# Sensors.net
KiCad netlist of a schematic drawn in Altium Designer
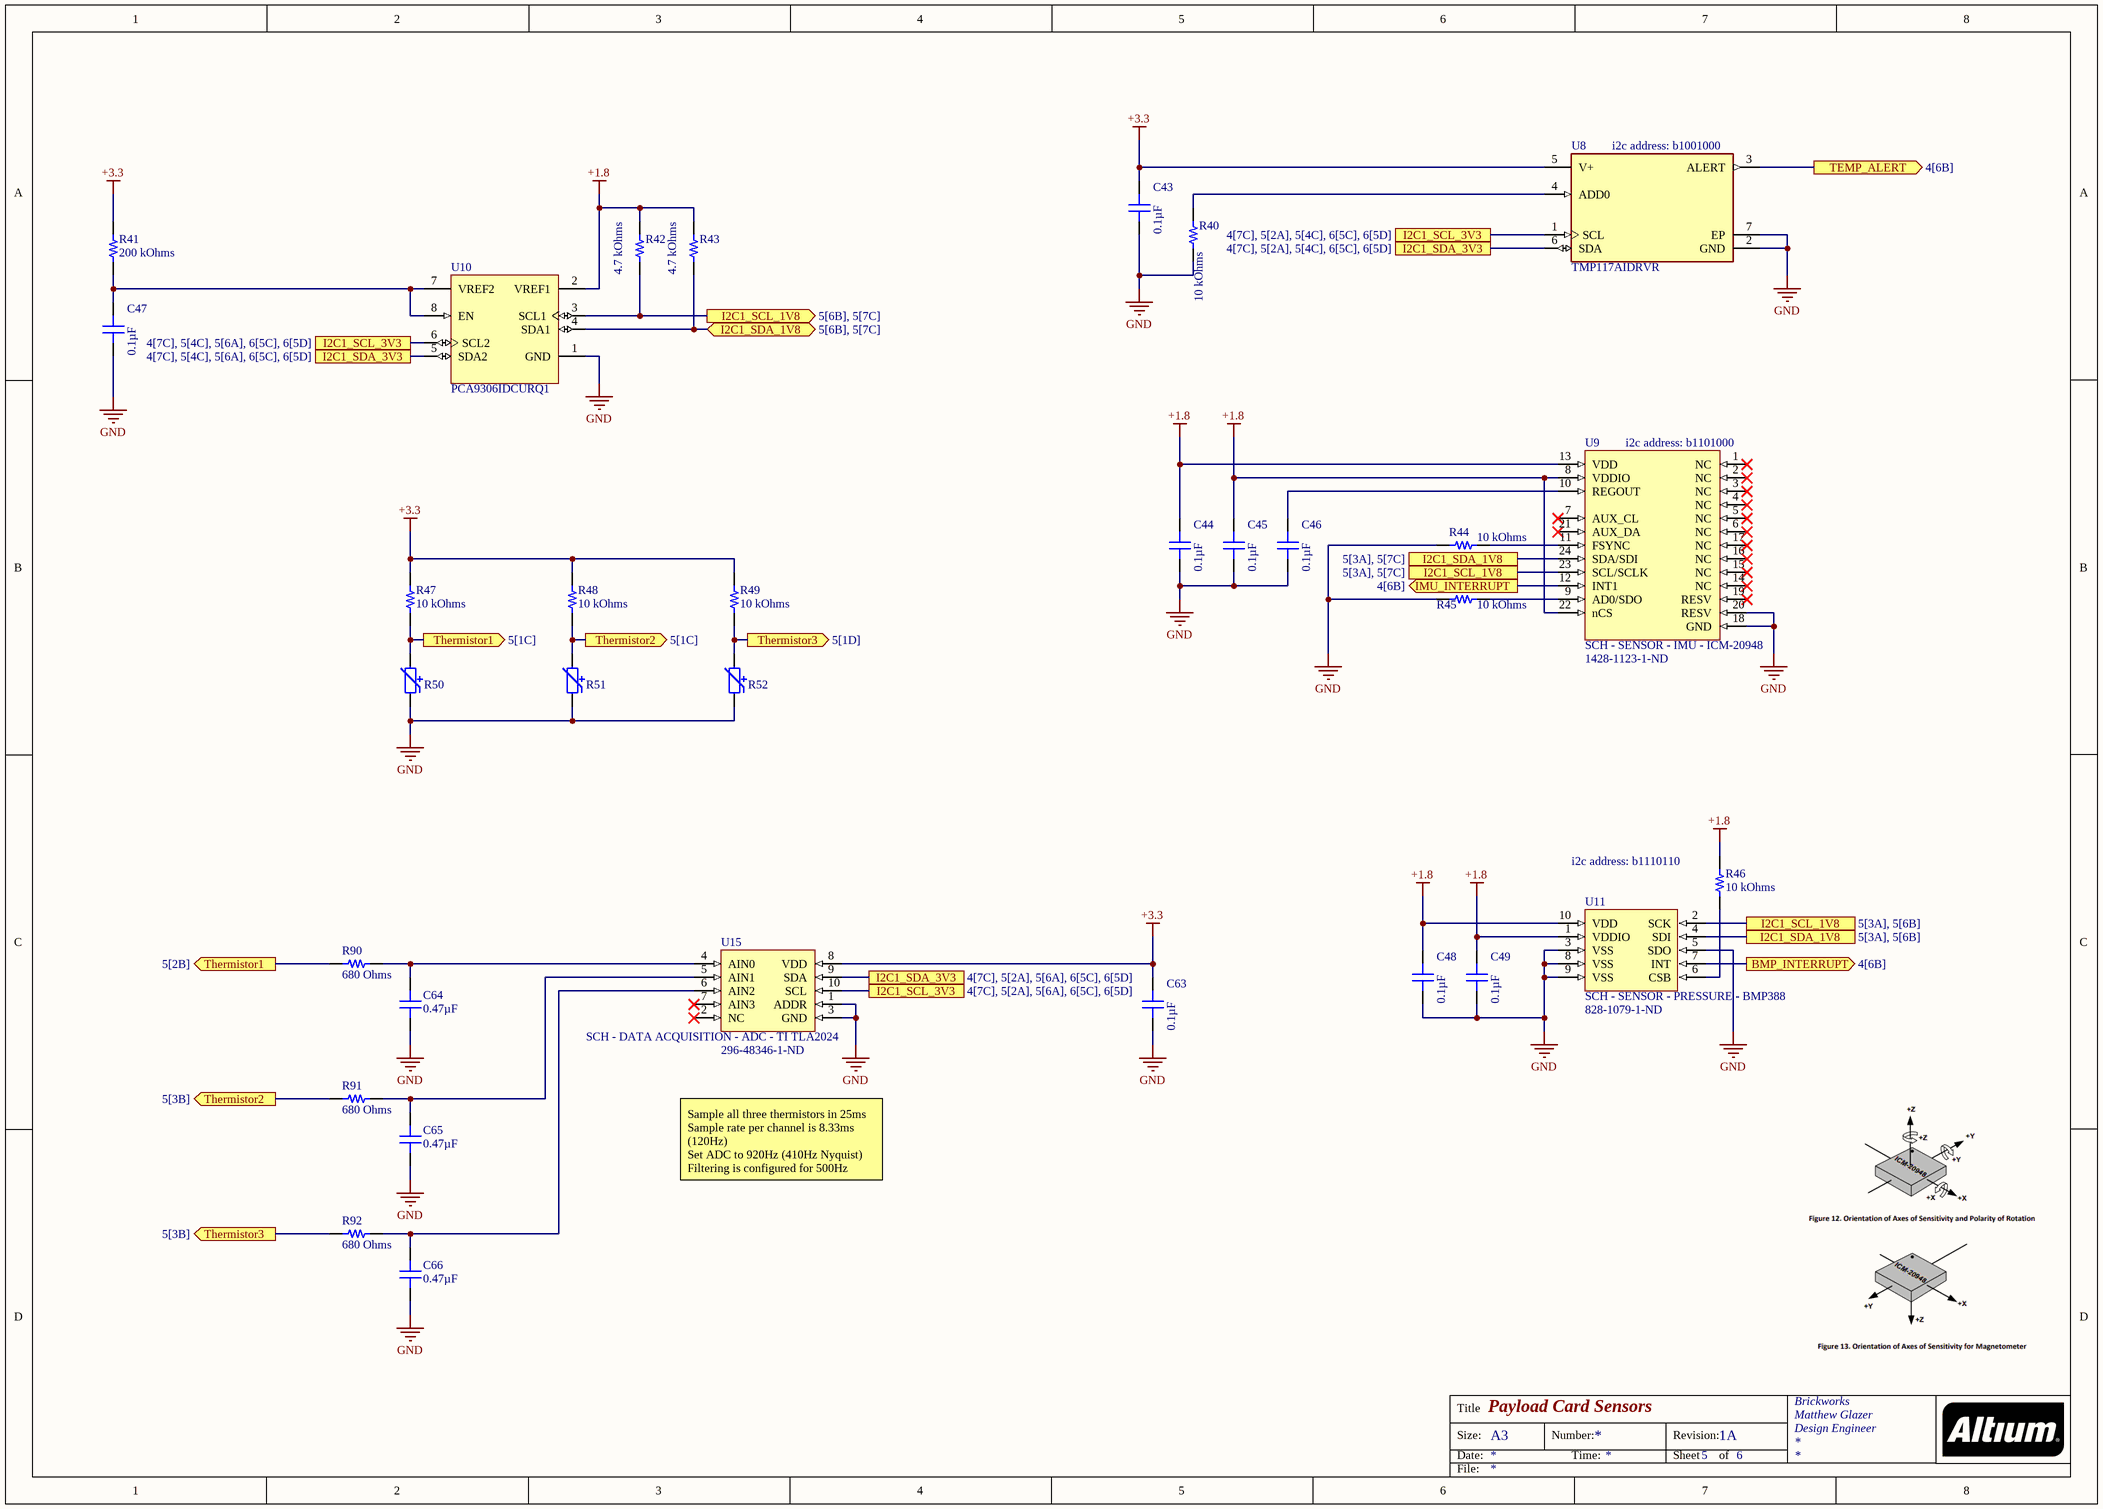
[diagram p0: Sensors.SchDoc]

(export (version "E")
  (design (tool "Eeschema 10.0.6"))
  (components
    (comp (ref "C43")
      (value "0.1µF")
      (footprint "CAP 0603_1608")
      (description "CAP CER 0.1UF 25V X7R 0603")
      (fields
        (field (name "PART NUMBER") "CL10B104KA8WPNC")
        (field (name "MANUFACTURER") "Samsung Electro-Mechanics")
      )
      (libsource (lib "Celestial Altium Library - altium_library") (part "Capacitor"))
    )
    (comp (ref "C44")
      (value "0.1µF")
      (footprint "CAP 0603_1608")
      (description "CAP CER 0.1UF 25V X7R 0603")
      (fields
        (field (name "PART NUMBER") "CL10B104KA8WPNC")
        (field (name "MANUFACTURER") "Samsung Electro-Mechanics")
      )
      (libsource (lib "Celestial Altium Library - altium_library") (part "Capacitor"))
    )
    (comp (ref "C45")
      (value "0.1µF")
      (footprint "CAP 0603_1608")
      (description "CAP CER 0.1UF 25V X7R 0603")
      (fields
        (field (name "PART NUMBER") "CL10B104KA8WPNC")
        (field (name "MANUFACTURER") "Samsung Electro-Mechanics")
      )
      (libsource (lib "Celestial Altium Library - altium_library") (part "Capacitor"))
    )
    (comp (ref "C46")
      (value "0.1µF")
      (footprint "CAP 0603_1608")
      (description "CAP CER 0.1UF 25V X7R 0603")
      (fields
        (field (name "PART NUMBER") "CL10B104KA8WPNC")
        (field (name "MANUFACTURER") "Samsung Electro-Mechanics")
      )
      (libsource (lib "Celestial Altium Library - altium_library") (part "Capacitor"))
    )
    (comp (ref "C47")
      (value "0.1µF")
      (footprint "CAP 0603_1608")
      (description "CAP CER 0.1UF 25V X7R 0603")
      (fields
        (field (name "PART NUMBER") "CL10B104KA8WPNC")
        (field (name "MANUFACTURER") "Samsung Electro-Mechanics")
      )
      (libsource (lib "Celestial Altium Library - altium_library") (part "Capacitor"))
    )
    (comp (ref "C48")
      (value "0.1µF")
      (footprint "CAP 0603_1608")
      (description "CAP CER 0.1UF 25V X7R 0603")
      (fields
        (field (name "PART NUMBER") "CL10B104KA8WPNC")
        (field (name "MANUFACTURER") "Samsung Electro-Mechanics")
      )
      (libsource (lib "Celestial Altium Library - altium_library") (part "Capacitor"))
    )
    (comp (ref "C49")
      (value "0.1µF")
      (footprint "CAP 0603_1608")
      (description "CAP CER 0.1UF 25V X7R 0603")
      (fields
        (field (name "PART NUMBER") "CL10B104KA8WPNC")
        (field (name "MANUFACTURER") "Samsung Electro-Mechanics")
      )
      (libsource (lib "Celestial Altium Library - altium_library") (part "Capacitor"))
    )
    (comp (ref "C63")
      (value "0.1µF")
      (footprint "CAP 0603_1608")
      (description "CAP CER 0.1UF 25V X7R 0603")
      (fields
        (field (name "PART NUMBER") "CL10B104KA8WPNC")
        (field (name "MANUFACTURER") "Samsung Electro-Mechanics")
      )
      (libsource (lib "Celestial Altium Library - altium_library") (part "Capacitor"))
    )
    (comp (ref "C64")
      (value "0.47µF")
      (footprint "CAP 0603_1608")
      (description "CAP CER 0.47UF 16V X5R 0603")
      (fields (field (name "PART NUMBER") "C0603C474K4PACTU") (field (name "MANUFACTURER") "KEMET"))
      (libsource (lib "Celestial Altium Library - altium_library") (part "Capacitor"))
    )
    (comp (ref "C65")
      (value "0.47µF")
      (footprint "CAP 0603_1608")
      (description "CAP CER 0.47UF 16V X5R 0603")
      (fields (field (name "PART NUMBER") "C0603C474K4PACTU") (field (name "MANUFACTURER") "KEMET"))
      (libsource (lib "Celestial Altium Library - altium_library") (part "Capacitor"))
    )
    (comp (ref "C66")
      (value "0.47µF")
      (footprint "CAP 0603_1608")
      (description "CAP CER 0.47UF 16V X5R 0603")
      (fields (field (name "PART NUMBER") "C0603C474K4PACTU") (field (name "MANUFACTURER") "KEMET"))
      (libsource (lib "Celestial Altium Library - altium_library") (part "Capacitor"))
    )
    (comp (ref "R40")
      (value "10 kOhms")
      (footprint "RES 0603_1608")
      (description "RES 10K OHM 5% 1/10W 0603")
      (fields
        (field (name "PART NUMBER") "RMCF0603JT10K0")
        (field (name "MANUFACTURER") "Stackpole Electronics Inc")
      )
      (libsource (lib "Celestial Altium Library - altium_library") (part "Resistor"))
    )
    (comp (ref "R41")
      (value "200 kOhms")
      (footprint "RES 0603_1608")
      (description "RES 200K OHM 1% 1/10W 0603")
      (fields
        (field (name "PART NUMBER") "RMCF0603FT200K")
        (field (name "MANUFACTURER") "Stackpole Electronics Inc")
      )
      (libsource (lib "Celestial Altium Library - altium_library") (part "Resistor"))
    )
    (comp (ref "R42")
      (value "4.7 kOhms")
      (footprint "RES 0603_1608")
      (description "RES 4.7K OHM 1% 1/10W 0603")
      (fields
        (field (name "PART NUMBER") "RMCF0603FT4K70")
        (field (name "MANUFACTURER") "Stackpole Electronics Inc")
      )
      (libsource (lib "Celestial Altium Library - altium_library") (part "Resistor"))
    )
    (comp (ref "R43")
      (value "4.7 kOhms")
      (footprint "RES 0603_1608")
      (description "RES 4.7K OHM 1% 1/10W 0603")
      (fields
        (field (name "PART NUMBER") "RMCF0603FT4K70")
        (field (name "MANUFACTURER") "Stackpole Electronics Inc")
      )
      (libsource (lib "Celestial Altium Library - altium_library") (part "Resistor"))
    )
    (comp (ref "R44")
      (value "10 kOhms")
      (footprint "RES 0603_1608")
      (description "RES 10K OHM 5% 1/10W 0603")
      (fields
        (field (name "PART NUMBER") "RMCF0603JT10K0")
        (field (name "MANUFACTURER") "Stackpole Electronics Inc")
      )
      (libsource (lib "Celestial Altium Library - altium_library") (part "Resistor"))
    )
    (comp (ref "R45")
      (value "10 kOhms")
      (footprint "RES 0603_1608")
      (description "RES 10K OHM 5% 1/10W 0603")
      (fields
        (field (name "PART NUMBER") "RMCF0603JT10K0")
        (field (name "MANUFACTURER") "Stackpole Electronics Inc")
      )
      (libsource (lib "Celestial Altium Library - altium_library") (part "Resistor"))
    )
    (comp (ref "R46")
      (value "10 kOhms")
      (footprint "RES 0603_1608")
      (description "RES 10K OHM 5% 1/10W 0603")
      (fields
        (field (name "PART NUMBER") "RMCF0603JT10K0")
        (field (name "MANUFACTURER") "Stackpole Electronics Inc")
      )
      (libsource (lib "Celestial Altium Library - altium_library") (part "Resistor"))
    )
    (comp (ref "R47")
      (value "10 kOhms")
      (footprint "RES 0603_1608")
      (description "RES 10K OHM 1% 1/10W 0603")
      (fields
        (field (name "PART NUMBER") "RMCF0603FT10K0")
        (field (name "MANUFACTURER") "Stackpole Electronics Inc")
      )
      (libsource (lib "Celestial Altium Library - altium_library") (part "Resistor"))
    )
    (comp (ref "R48")
      (value "10 kOhms")
      (footprint "RES 0603_1608")
      (description "RES 10K OHM 1% 1/10W 0603")
      (fields
        (field (name "PART NUMBER") "RMCF0603FT10K0")
        (field (name "MANUFACTURER") "Stackpole Electronics Inc")
      )
      (libsource (lib "Celestial Altium Library - altium_library") (part "Resistor"))
    )
    (comp (ref "R49")
      (value "10 kOhms")
      (footprint "RES 0603_1608")
      (description "RES 10K OHM 1% 1/10W 0603")
      (fields
        (field (name "PART NUMBER") "RMCF0603FT10K0")
        (field (name "MANUFACTURER") "Stackpole Electronics Inc")
      )
      (libsource (lib "Celestial Altium Library - altium_library") (part "Resistor"))
    )
    (comp (ref "R50")
      (value "10 kOhms")
      (footprint "PTC 0402_1005")
      (description "SENSOR PTC 10KOHM 1% X1SON")
      (fields (field (name "MANUFACTURER") "Texas Instruments") (field (name "PART NUMBER") "TMP6131DECR"))
      (libsource (lib "Celestial Altium Library - altium_library") (part "Thermistor PTC"))
    )
    (comp (ref "R51")
      (value "10 kOhms")
      (footprint "PTC 0402_1005")
      (description "SENSOR PTC 10KOHM 1% X1SON")
      (fields (field (name "MANUFACTURER") "Texas Instruments") (field (name "PART NUMBER") "TMP6131DECR"))
      (libsource (lib "Celestial Altium Library - altium_library") (part "Thermistor PTC"))
    )
    (comp (ref "R52")
      (value "10 kOhms")
      (footprint "PTC 0402_1005")
      (description "SENSOR PTC 10KOHM 1% X1SON")
      (fields (field (name "MANUFACTURER") "Texas Instruments") (field (name "PART NUMBER") "TMP6131DECR"))
      (libsource (lib "Celestial Altium Library - altium_library") (part "Thermistor PTC"))
    )
    (comp (ref "R90")
      (value "680 Ohms")
      (footprint "RES 0603_1608")
      (description "RES 680 OHM 1% 1/10W 0603")
      (fields
        (field (name "PART NUMBER") "RMCF0603FT680R")
        (field (name "MANUFACTURER") "Stackpole Electronics Inc")
      )
      (libsource (lib "Celestial Altium Library - altium_library") (part "Resistor"))
    )
    (comp (ref "R91")
      (value "680 Ohms")
      (footprint "RES 0603_1608")
      (description "RES 680 OHM 1% 1/10W 0603")
      (fields
        (field (name "PART NUMBER") "RMCF0603FT680R")
        (field (name "MANUFACTURER") "Stackpole Electronics Inc")
      )
      (libsource (lib "Celestial Altium Library - altium_library") (part "Resistor"))
    )
    (comp (ref "R92")
      (value "680 Ohms")
      (footprint "RES 0603_1608")
      (description "RES 680 OHM 1% 1/10W 0603")
      (fields
        (field (name "PART NUMBER") "RMCF0603FT680R")
        (field (name "MANUFACTURER") "Stackpole Electronics Inc")
      )
      (libsource (lib "Celestial Altium Library - altium_library") (part "Resistor"))
    )
    (comp (ref "U8")
      (value "TMP117AIDRVR")
      (footprint "FP-DRV0006A-MFG")
      (description "TEMPERATURE SENSOR")
      (fields
        (field (name "OCTOPART") "https://octopart.com/tmp117aidrvr-texas+instruments-95511044")
        (field (name "MANUFACTURER") "Texas Instruments")
      )
      (libsource (lib "Altium Content Vault") (part "bceab6869a9cb85cf5675529ee35ce4"))
    )
    (comp (ref "U9")
      (value "SCH - SENSOR - IMU - ICM-20948")
      (footprint "PCB - LEADLESS - QFN - TDK 24-TFQFN")
      (fields (field (name "SUPPLIER PART NUMBER 1") "1428-1123-1-ND"))
      (libsource (lib "HAB_ICs") (part "SCH - SENSOR - IMU - ICM-20948"))
    )
    (comp (ref "U10")
      (value "PCA9306IDCURQ1")
      (footprint "DCU0008A_M")
      (fields (field (name "MANUFACTURER") "Texas Instruments"))
      (libsource (lib "Altium Content Vault") (part "TI-PCA9306-Q1-US8_DCU-8"))
    )
    (comp (ref "U11")
      (value "SCH - SENSOR - PRESSURE - BMP388")
      (footprint "PCB - LEADLESS - BOSCH LGA10")
      (fields (field (name "SUPPLIER PART NUMBER 1") "828-1079-1-ND"))
      (libsource (lib "HAB_ICs") (part "SCH - SENSOR - PRESSURE - BMP388"))
    )
    (comp (ref "U15")
      (value "SCH - DATA ACQUISITION - ADC - TI TLA2024")
      (footprint "PCB - LEADLESS - QFN - TI X2QFN-10")
      (fields (field (name "SUPPLIER PART NUMBER 1") "296-48346-1-ND"))
      (libsource (lib "HAB_ICs") (part "SCH - DATA ACQUISITION - ADC - TI TLA2024"))
    )
  )
  (nets
    (net (code "1") (name "+1.8") (class "Default")
      (node (ref "C44") (pin "2") (pinfunction "2_2") (pintype "passive"))
      (node (ref "C45") (pin "2") (pinfunction "2_2") (pintype "passive"))
      (node (ref "C48") (pin "2") (pinfunction "2_2") (pintype "passive"))
      (node (ref "C49") (pin "2") (pinfunction "2_2") (pintype "passive"))
      (node (ref "R42") (pin "2") (pinfunction "2_2") (pintype "passive"))
      (node (ref "R43") (pin "2") (pinfunction "2_2") (pintype "passive"))
      (node (ref "R46") (pin "1") (pinfunction "1_1") (pintype "passive"))
      (node (ref "U10") (pin "2") (pinfunction "VREF1_2") (pintype "power_in"))
      (node (ref "U11") (pin "1") (pinfunction "VDDIO_1") (pintype "input"))
      (node (ref "U11") (pin "10") (pinfunction "VDD_10") (pintype "input"))
      (node (ref "U9") (pin "13") (pinfunction "VDD_13") (pintype "input"))
      (node (ref "U9") (pin "22") (pinfunction "nCS_22") (pintype "input"))
      (node (ref "U9") (pin "8") (pinfunction "VDDIO_8") (pintype "input"))
    )
    (net (code "2") (name "+3.3") (class "Default")
      (node (ref "C43") (pin "2") (pinfunction "2_2") (pintype "passive"))
      (node (ref "C63") (pin "2") (pinfunction "2_2") (pintype "passive"))
      (node (ref "R41") (pin "2") (pinfunction "2_2") (pintype "passive"))
      (node (ref "R47") (pin "2") (pinfunction "2_2") (pintype "passive"))
      (node (ref "R48") (pin "2") (pinfunction "2_2") (pintype "passive"))
      (node (ref "R49") (pin "2") (pinfunction "2_2") (pintype "passive"))
      (node (ref "U15") (pin "8") (pinfunction "VDD_8") (pintype "input"))
      (node (ref "U8") (pin "5") (pinfunction "V+_5") (pintype "power_in"))
    )
    (net (code "3") (name "/BMP_INTERRUPT") (class "Default")
      (node (ref "U11") (pin "7") (pinfunction "INT_7") (pintype "input"))
    )
    (net (code "4") (name "/I2C1_SCL_1V8") (class "Default")
      (node (ref "R42") (pin "1") (pinfunction "1_1") (pintype "passive"))
      (node (ref "U10") (pin "3") (pinfunction "SCL1_3") (pintype "bidirectional"))
      (node (ref "U11") (pin "2") (pinfunction "SCK_2") (pintype "input"))
      (node (ref "U9") (pin "23") (pinfunction "SCL/SCLK_23") (pintype "input"))
    )
    (net (code "5") (name "/I2C1_SCL_3V3") (class "Default")
      (node (ref "U10") (pin "6") (pinfunction "SCL2_6") (pintype "bidirectional"))
      (node (ref "U15") (pin "10") (pinfunction "SCL_10") (pintype "input"))
      (node (ref "U8") (pin "1") (pinfunction "SCL_1") (pintype "input"))
    )
    (net (code "6") (name "/I2C1_SDA_1V8") (class "Default")
      (node (ref "R43") (pin "1") (pinfunction "1_1") (pintype "passive"))
      (node (ref "U10") (pin "4") (pinfunction "SDA1_4") (pintype "bidirectional"))
      (node (ref "U11") (pin "4") (pinfunction "SDI_4") (pintype "input"))
      (node (ref "U9") (pin "24") (pinfunction "SDA/SDI_24") (pintype "input"))
    )
    (net (code "7") (name "/I2C1_SDA_3V3") (class "Default")
      (node (ref "U10") (pin "5") (pinfunction "SDA2_5") (pintype "bidirectional"))
      (node (ref "U15") (pin "9") (pinfunction "SDA_9") (pintype "input"))
      (node (ref "U8") (pin "6") (pinfunction "SDA_6") (pintype "bidirectional"))
    )
    (net (code "8") (name "/IMU_INTERRUPT") (class "Default")
      (node (ref "U9") (pin "12") (pinfunction "INT1_12") (pintype "input"))
    )
    (net (code "9") (name "/TEMP_ALERT") (class "Default")
      (node (ref "U8") (pin "3") (pinfunction "ALERT_3") (pintype "output"))
    )
    (net (code "10") (name "/Thermistor1") (class "Default")
      (node (ref "R47") (pin "1") (pinfunction "1_1") (pintype "passive"))
      (node (ref "R50") (pin "2") (pinfunction "2_2") (pintype "passive"))
      (node (ref "R90") (pin "1") (pinfunction "1_1") (pintype "passive"))
    )
    (net (code "11") (name "/Thermistor2") (class "Default")
      (node (ref "R48") (pin "1") (pinfunction "1_1") (pintype "passive"))
      (node (ref "R51") (pin "2") (pinfunction "2_2") (pintype "passive"))
      (node (ref "R91") (pin "1") (pinfunction "1_1") (pintype "passive"))
    )
    (net (code "12") (name "/Thermistor3") (class "Default")
      (node (ref "R49") (pin "1") (pinfunction "1_1") (pintype "passive"))
      (node (ref "R52") (pin "2") (pinfunction "2_2") (pintype "passive"))
      (node (ref "R92") (pin "1") (pinfunction "1_1") (pintype "passive"))
    )
    (net (code "13") (name "GND") (class "Default")
      (node (ref "C43") (pin "1") (pinfunction "1_1") (pintype "passive"))
      (node (ref "C44") (pin "1") (pinfunction "1_1") (pintype "passive"))
      (node (ref "C45") (pin "1") (pinfunction "1_1") (pintype "passive"))
      (node (ref "C46") (pin "1") (pinfunction "1_1") (pintype "passive"))
      (node (ref "C47") (pin "1") (pinfunction "1_1") (pintype "passive"))
      (node (ref "C48") (pin "1") (pinfunction "1_1") (pintype "passive"))
      (node (ref "C49") (pin "1") (pinfunction "1_1") (pintype "passive"))
      (node (ref "C63") (pin "1") (pinfunction "1_1") (pintype "passive"))
      (node (ref "C64") (pin "1") (pinfunction "1_1") (pintype "passive"))
      (node (ref "C65") (pin "1") (pinfunction "1_1") (pintype "passive"))
      (node (ref "C66") (pin "1") (pinfunction "1_1") (pintype "passive"))
      (node (ref "R40") (pin "1") (pinfunction "1_1") (pintype "passive"))
      (node (ref "R44") (pin "2") (pinfunction "2_2") (pintype "passive"))
      (node (ref "R45") (pin "2") (pinfunction "2_2") (pintype "passive"))
      (node (ref "R50") (pin "1") (pinfunction "1_1") (pintype "passive"))
      (node (ref "R51") (pin "1") (pinfunction "1_1") (pintype "passive"))
      (node (ref "R52") (pin "1") (pinfunction "1_1") (pintype "passive"))
      (node (ref "U10") (pin "1") (pinfunction "GND_1") (pintype "power_in"))
      (node (ref "U11") (pin "3") (pinfunction "VSS_3") (pintype "input"))
      (node (ref "U11") (pin "5") (pinfunction "SDO_5") (pintype "input"))
      (node (ref "U11") (pin "8") (pinfunction "VSS_8") (pintype "input"))
      (node (ref "U11") (pin "9") (pinfunction "VSS_9") (pintype "input"))
      (node (ref "U15") (pin "1") (pinfunction "ADDR_1") (pintype "input"))
      (node (ref "U15") (pin "3") (pinfunction "GND_3") (pintype "input"))
      (node (ref "U8") (pin "2") (pinfunction "GND_2") (pintype "power_in"))
      (node (ref "U8") (pin "7") (pinfunction "EP_7") (pintype "passive"))
      (node (ref "U9") (pin "18") (pinfunction "GND_18") (pintype "input"))
      (node (ref "U9") (pin "20") (pinfunction "RESV_20") (pintype "input"))
    )
    (net (code "14") (name "Net-(U8-ADD0)") (class "Default")
      (node (ref "R40") (pin "2") (pinfunction "2_2") (pintype "passive"))
      (node (ref "U8") (pin "4") (pinfunction "ADD0_4") (pintype "input"))
    )
    (net (code "15") (name "Net-(U9-AD0{slash}SDO)") (class "Default")
      (node (ref "R45") (pin "1") (pinfunction "1_1") (pintype "passive"))
      (node (ref "U9") (pin "9") (pinfunction "AD0/SDO_9") (pintype "input"))
    )
    (net (code "16") (name "Net-(U9-FSYNC)") (class "Default")
      (node (ref "R44") (pin "1") (pinfunction "1_1") (pintype "passive"))
      (node (ref "U9") (pin "11") (pinfunction "FSYNC_11") (pintype "input"))
    )
    (net (code "17") (name "Net-(U9-REGOUT)") (class "Default")
      (node (ref "C46") (pin "2") (pinfunction "2_2") (pintype "passive"))
      (node (ref "U9") (pin "10") (pinfunction "REGOUT_10") (pintype "input"))
    )
    (net (code "18") (name "Net-(U10-EN)") (class "Default")
      (node (ref "C47") (pin "2") (pinfunction "2_2") (pintype "passive"))
      (node (ref "R41") (pin "1") (pinfunction "1_1") (pintype "passive"))
      (node (ref "U10") (pin "7") (pinfunction "VREF2_7") (pintype "power_in"))
      (node (ref "U10") (pin "8") (pinfunction "EN_8") (pintype "input"))
    )
    (net (code "19") (name "Net-(U11-CSB)") (class "Default")
      (node (ref "R46") (pin "2") (pinfunction "2_2") (pintype "passive"))
      (node (ref "U11") (pin "6") (pinfunction "CSB_6") (pintype "input"))
    )
    (net (code "20") (name "Net-(U15-AIN0)") (class "Default")
      (node (ref "C64") (pin "2") (pinfunction "2_2") (pintype "passive"))
      (node (ref "R90") (pin "2") (pinfunction "2_2") (pintype "passive"))
      (node (ref "U15") (pin "4") (pinfunction "AIN0_4") (pintype "input"))
    )
    (net (code "21") (name "Net-(U15-AIN1)") (class "Default")
      (node (ref "C65") (pin "2") (pinfunction "2_2") (pintype "passive"))
      (node (ref "R91") (pin "2") (pinfunction "2_2") (pintype "passive"))
      (node (ref "U15") (pin "5") (pinfunction "AIN1_5") (pintype "input"))
    )
    (net (code "22") (name "Net-(U15-AIN2)") (class "Default")
      (node (ref "C66") (pin "2") (pinfunction "2_2") (pintype "passive"))
      (node (ref "R92") (pin "2") (pinfunction "2_2") (pintype "passive"))
      (node (ref "U15") (pin "6") (pinfunction "AIN2_6") (pintype "input"))
    )
    (net (code "23") (name "unconnected-(U9-AUX_CL-Pad7)") (class "Default")
      (node (ref "U9") (pin "7") (pinfunction "AUX_CL_7") (pintype "input+no_connect"))
    )
    (net (code "24") (name "unconnected-(U9-AUX_DA-Pad21)") (class "Default")
      (node (ref "U9") (pin "21") (pinfunction "AUX_DA_21") (pintype "input+no_connect"))
    )
    (net (code "25") (name "unconnected-(U9-NC-Pad1)") (class "Default")
      (node (ref "U9") (pin "1") (pinfunction "NC_1") (pintype "input+no_connect"))
    )
    (net (code "26") (name "unconnected-(U9-NC-Pad2)") (class "Default")
      (node (ref "U9") (pin "2") (pinfunction "NC_2") (pintype "input+no_connect"))
    )
    (net (code "27") (name "unconnected-(U9-NC-Pad3)") (class "Default")
      (node (ref "U9") (pin "3") (pinfunction "NC_3") (pintype "input+no_connect"))
    )
    (net (code "28") (name "unconnected-(U9-NC-Pad4)") (class "Default")
      (node (ref "U9") (pin "4") (pinfunction "NC_4") (pintype "input+no_connect"))
    )
    (net (code "29") (name "unconnected-(U9-NC-Pad5)") (class "Default")
      (node (ref "U9") (pin "5") (pinfunction "NC_5") (pintype "input+no_connect"))
    )
    (net (code "30") (name "unconnected-(U9-NC-Pad6)") (class "Default")
      (node (ref "U9") (pin "6") (pinfunction "NC_6") (pintype "input+no_connect"))
    )
    (net (code "31") (name "unconnected-(U9-NC-Pad14)") (class "Default")
      (node (ref "U9") (pin "14") (pinfunction "NC_14") (pintype "input+no_connect"))
    )
    (net (code "32") (name "unconnected-(U9-NC-Pad15)") (class "Default")
      (node (ref "U9") (pin "15") (pinfunction "NC_15") (pintype "input+no_connect"))
    )
    (net (code "33") (name "unconnected-(U9-NC-Pad16)") (class "Default")
      (node (ref "U9") (pin "16") (pinfunction "NC_16") (pintype "input+no_connect"))
    )
    (net (code "34") (name "unconnected-(U9-NC-Pad17)") (class "Default")
      (node (ref "U9") (pin "17") (pinfunction "NC_17") (pintype "input+no_connect"))
    )
    (net (code "35") (name "unconnected-(U9-RESV-Pad19)") (class "Default")
      (node (ref "U9") (pin "19") (pinfunction "RESV_19") (pintype "input+no_connect"))
    )
    (net (code "36") (name "unconnected-(U15-AIN3-Pad7)") (class "Default")
      (node (ref "U15") (pin "7") (pinfunction "AIN3_7") (pintype "input+no_connect"))
    )
    (net (code "37") (name "unconnected-(U15-NC-Pad2)") (class "Default")
      (node (ref "U15") (pin "2") (pinfunction "NC_2") (pintype "input+no_connect"))
    )
  )
)
